# 04_ADC.net
KiCad netlist of a schematic drawn in Altium Designer
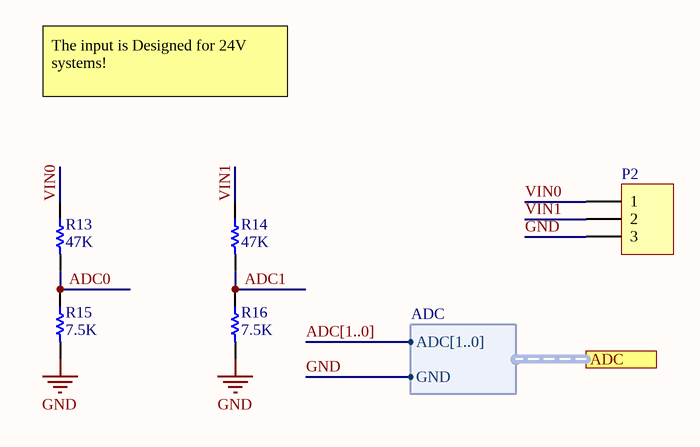
[diagram p0: [04] ADC.SchDoc]

(export (version "E")
  (design (tool "Eeschema 10.0.6"))
  (components
    (comp (ref "P2")
      (value "Header 3")
      (footprint "MY_ECH381H_03P")
      (description "Header, 3-Pin")
      (fields (field (name "ASID PART NUMBER") "Header 3-AS"))
      (libsource (lib "Mylib Rev 4") (part "Header 3"))
    )
    (comp (ref "R13")
      (value "47K")
      (footprint "MY_0805")
      (description "Standard resistor")
      (fields (field (name "ASID PART NUMBER") "Res-AS"))
      (libsource (lib "Mylib Rev 4") (part "Res"))
    )
    (comp (ref "R14")
      (value "47K")
      (footprint "MY_0805")
      (description "Standard resistor")
      (fields (field (name "ASID PART NUMBER") "Res-AS"))
      (libsource (lib "Mylib Rev 4") (part "Res"))
    )
    (comp (ref "R15")
      (value "7.5K")
      (footprint "MY_0805")
      (description "Standard resistor")
      (fields (field (name "ASID PART NUMBER") "Res-AS"))
      (libsource (lib "Mylib Rev 4") (part "Res"))
    )
    (comp (ref "R16")
      (value "7.5K")
      (footprint "MY_0805")
      (description "Standard resistor")
      (fields (field (name "ASID PART NUMBER") "Res-AS"))
      (libsource (lib "Mylib Rev 4") (part "Res"))
    )
  )
  (nets
    (net (code "2") (name "/ADC0") (class "Default")
      (node (ref "R13") (pin "2") (pinfunction "2_2") (pintype "passive"))
      (node (ref "R15") (pin "1") (pinfunction "1_1") (pintype "passive"))
    )
    (net (code "3") (name "/ADC1") (class "Default")
      (node (ref "R14") (pin "2") (pinfunction "2_2") (pintype "passive"))
      (node (ref "R16") (pin "1") (pinfunction "1_1") (pintype "passive"))
    )
    (net (code "5") (name "/VIN0") (class "Default")
      (node (ref "P2") (pin "1") (pinfunction "1_1") (pintype "passive"))
      (node (ref "R13") (pin "1") (pinfunction "1_1") (pintype "passive"))
    )
    (net (code "6") (name "/VIN1") (class "Default")
      (node (ref "P2") (pin "2") (pinfunction "2_2") (pintype "passive"))
      (node (ref "R14") (pin "1") (pinfunction "1_1") (pintype "passive"))
    )
    (net (code "8") (name "GND") (class "Default")
      (node (ref "P2") (pin "3") (pinfunction "3_3") (pintype "passive"))
      (node (ref "R15") (pin "2") (pinfunction "2_2") (pintype "passive"))
      (node (ref "R16") (pin "2") (pinfunction "2_2") (pintype "passive"))
    )
  )
)
